# full_Bridge_v2.net
KiCad netlist of a schematic drawn in EAGLE
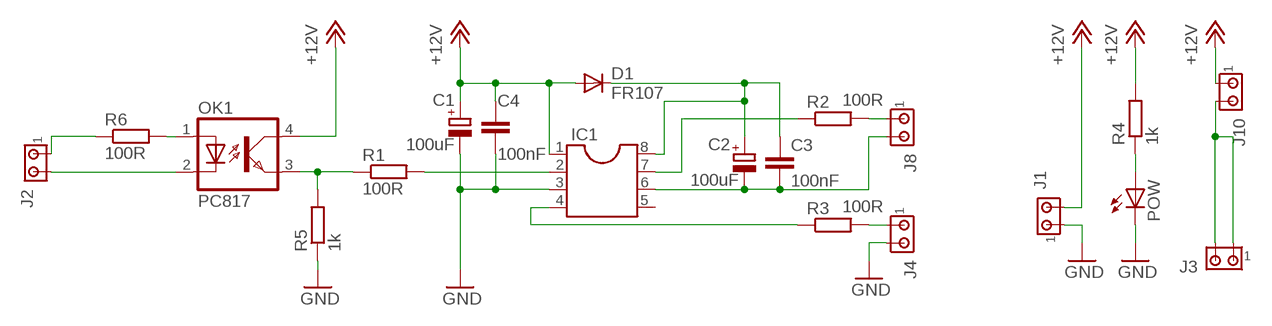
[diagram p0: schematic, sheet 1]

(export (version "E")
  (design (tool "Eeschema 10.0.6"))
  (components
    (comp (ref "C1")
      (value "100uF")
      (footprint "eagle-import:E2,5-6E")
      (libsource (lib "eagle-import") (part "CPOL-EUE2,5-6E"))
    )
    (comp (ref "C2")
      (value "100uF")
      (footprint "eagle-import:E2,5-7")
      (libsource (lib "eagle-import") (part "CPOL-EUE2.5-7"))
    )
    (comp (ref "C3")
      (value "100nF")
      (footprint "eagle-import:C050-024X044")
      (libsource (lib "eagle-import") (part "C-EU050-024X044"))
    )
    (comp (ref "C4")
      (value "100nF")
      (footprint "eagle-import:C050-024X044")
      (libsource (lib "eagle-import") (part "C-EU050-024X044"))
    )
    (comp (ref "D1")
      (value "FR107")
      (footprint "eagle-import:DO41-10")
      (libsource (lib "eagle-import") (part "1N4004"))
    )
    (comp (ref "IC1")
      (value "DIL8")
      (footprint "eagle-import:DIL08")
      (libsource (lib "eagle-import") (part "DIL8"))
    )
    (comp (ref "J1")
      (value "MTA02-100")
      (footprint "eagle-import:10X02MTA")
      (libsource (lib "eagle-import") (part "MTA02-100"))
    )
    (comp (ref "J2")
      (value "MTA02-100")
      (footprint "eagle-import:10X02MTA")
      (libsource (lib "eagle-import") (part "MTA02-100"))
    )
    (comp (ref "J3")
      (value "MTA02-100")
      (footprint "eagle-import:10X02MTA")
      (libsource (lib "eagle-import") (part "MTA02-100"))
    )
    (comp (ref "J4")
      (value "MTA02-100")
      (footprint "eagle-import:10X02MTA")
      (libsource (lib "eagle-import") (part "MTA02-100"))
    )
    (comp (ref "J8")
      (value "MTA02-100")
      (footprint "eagle-import:10X02MTA")
      (libsource (lib "eagle-import") (part "MTA02-100"))
    )
    (comp (ref "J10")
      (value "MTA02-100")
      (footprint "eagle-import:10X02MTA")
      (libsource (lib "eagle-import") (part "MTA02-100"))
    )
    (comp (ref "OK1")
      (value "PC817")
      (footprint "eagle-import:DIL04")
      (fields (field (name "MPN") "PC817X4J000F"))
      (libsource (lib "eagle-import") (part "PC817"))
    )
    (comp (ref "POW")
      (value "LED3MM")
      (footprint "eagle-import:LED3MM")
      (libsource (lib "eagle-import") (part "LED3MM"))
    )
    (comp (ref "R1")
      (value "100R")
      (footprint "eagle-import:0204_7")
      (libsource (lib "eagle-import") (part "R-EU_0204/7"))
    )
    (comp (ref "R2")
      (value "100R")
      (footprint "eagle-import:0204_7")
      (libsource (lib "eagle-import") (part "R-EU_0204/7"))
    )
    (comp (ref "R3")
      (value "100R")
      (footprint "eagle-import:0207_12")
      (libsource (lib "eagle-import") (part "R-EU_0207/12"))
    )
    (comp (ref "R4")
      (value "1k")
      (footprint "eagle-import:0204_7")
      (libsource (lib "eagle-import") (part "R-EU_0204/7"))
    )
    (comp (ref "R5")
      (value "1k")
      (footprint "eagle-import:0204_7")
      (libsource (lib "eagle-import") (part "R-EU_0204/7"))
    )
    (comp (ref "R6")
      (value "100R")
      (footprint "eagle-import:0204_7")
      (libsource (lib "eagle-import") (part "R-EU_0204/7"))
    )
  )
  (nets
    (net (code "1") (name "+12V") (class "Default")
      (node (ref "C1") (pin "+") (pinfunction "+_+") (pintype "passive"))
      (node (ref "C4") (pin "1") (pinfunction "1_1") (pintype "passive"))
      (node (ref "D1") (pin "A") (pinfunction "A_A") (pintype "passive"))
      (node (ref "IC1") (pin "1") (pinfunction "1_1") (pintype "passive"))
      (node (ref "J1") (pin "2") (pinfunction "2_2") (pintype "passive"))
      (node (ref "J10") (pin "1") (pinfunction "1_1") (pintype "passive"))
      (node (ref "OK1") (pin "4") (pinfunction "COL_4") (pintype "passive"))
      (node (ref "R4") (pin "2") (pinfunction "2_2") (pintype "passive"))
    )
    (net (code "2") (name "GND") (class "Default")
      (node (ref "C1") (pin "-") (pinfunction "-_-") (pintype "passive"))
      (node (ref "C4") (pin "2") (pinfunction "2_2") (pintype "passive"))
      (node (ref "IC1") (pin "3") (pinfunction "3_3") (pintype "passive"))
      (node (ref "J1") (pin "1") (pinfunction "1_1") (pintype "passive"))
      (node (ref "J4") (pin "2") (pinfunction "2_2") (pintype "passive"))
      (node (ref "POW") (pin "K") (pinfunction "C_K") (pintype "passive"))
      (node (ref "R5") (pin "1") (pinfunction "1_1") (pintype "passive"))
    )
    (net (code "3") (name "Net-(C2-Pad+)") (class "Default")
      (node (ref "C2") (pin "+") (pinfunction "+_+") (pintype "passive"))
      (node (ref "C3") (pin "1") (pinfunction "1_1") (pintype "passive"))
      (node (ref "D1") (pin "C") (pinfunction "C_C") (pintype "passive"))
      (node (ref "IC1") (pin "8") (pinfunction "8_8") (pintype "passive"))
    )
    (net (code "4") (name "Net-(C2-Pad-)") (class "Default")
      (node (ref "C2") (pin "-") (pinfunction "-_-") (pintype "passive"))
      (node (ref "C3") (pin "2") (pinfunction "2_2") (pintype "passive"))
      (node (ref "IC1") (pin "6") (pinfunction "6_6") (pintype "passive"))
      (node (ref "J8") (pin "2") (pinfunction "2_2") (pintype "passive"))
    )
    (net (code "5") (name "Net-(IC1-Pad2)") (class "Default")
      (node (ref "IC1") (pin "2") (pinfunction "2_2") (pintype "passive"))
      (node (ref "R1") (pin "2") (pinfunction "2_2") (pintype "passive"))
    )
    (net (code "6") (name "Net-(IC1-Pad4)") (class "Default")
      (node (ref "IC1") (pin "4") (pinfunction "4_4") (pintype "passive"))
      (node (ref "R3") (pin "1") (pinfunction "1_1") (pintype "passive"))
    )
    (net (code "7") (name "Net-(IC1-Pad7)") (class "Default")
      (node (ref "IC1") (pin "7") (pinfunction "7_7") (pintype "passive"))
      (node (ref "R2") (pin "1") (pinfunction "1_1") (pintype "passive"))
    )
    (net (code "8") (name "Net-(J2-Pad1)") (class "Default")
      (node (ref "J2") (pin "1") (pinfunction "1_1") (pintype "passive"))
      (node (ref "R6") (pin "1") (pinfunction "1_1") (pintype "passive"))
    )
    (net (code "9") (name "Net-(J4-Pad1)") (class "Default")
      (node (ref "J4") (pin "1") (pinfunction "1_1") (pintype "passive"))
      (node (ref "R3") (pin "2") (pinfunction "2_2") (pintype "passive"))
    )
    (net (code "10") (name "Net-(J8-Pad1)") (class "Default")
      (node (ref "J8") (pin "1") (pinfunction "1_1") (pintype "passive"))
      (node (ref "R2") (pin "2") (pinfunction "2_2") (pintype "passive"))
    )
    (net (code "11") (name "Net-(J10-Pad2)") (class "Default")
      (node (ref "J10") (pin "2") (pinfunction "2_2") (pintype "passive"))
      (node (ref "J3") (pin "1") (pinfunction "1_1") (pintype "passive"))
      (node (ref "J3") (pin "2") (pinfunction "2_2") (pintype "passive"))
    )
    (net (code "12") (name "Net-(OK1-A)") (class "Default")
      (node (ref "OK1") (pin "1") (pinfunction "A_1") (pintype "passive"))
      (node (ref "R6") (pin "2") (pinfunction "2_2") (pintype "passive"))
    )
    (net (code "13") (name "Net-(OK1-C)") (class "Default")
      (node (ref "J2") (pin "2") (pinfunction "2_2") (pintype "passive"))
      (node (ref "OK1") (pin "2") (pinfunction "C_2") (pintype "passive"))
    )
    (net (code "14") (name "Net-(OK1-EMIT)") (class "Default")
      (node (ref "OK1") (pin "3") (pinfunction "EMIT_3") (pintype "passive"))
      (node (ref "R1") (pin "1") (pinfunction "1_1") (pintype "passive"))
      (node (ref "R5") (pin "2") (pinfunction "2_2") (pintype "passive"))
    )
    (net (code "15") (name "Net-(POW-PadA)") (class "Default")
      (node (ref "POW") (pin "A") (pinfunction "A_A") (pintype "passive"))
      (node (ref "R4") (pin "1") (pinfunction "1_1") (pintype "passive"))
    )
    (net (code "16") (name "unconnected-(IC1-Pad5)") (class "Default")
      (node (ref "IC1") (pin "5") (pinfunction "5_5") (pintype "passive"))
    )
  )
)
